# Power_management.net
KiCad netlist of a schematic drawn in Altium Designer
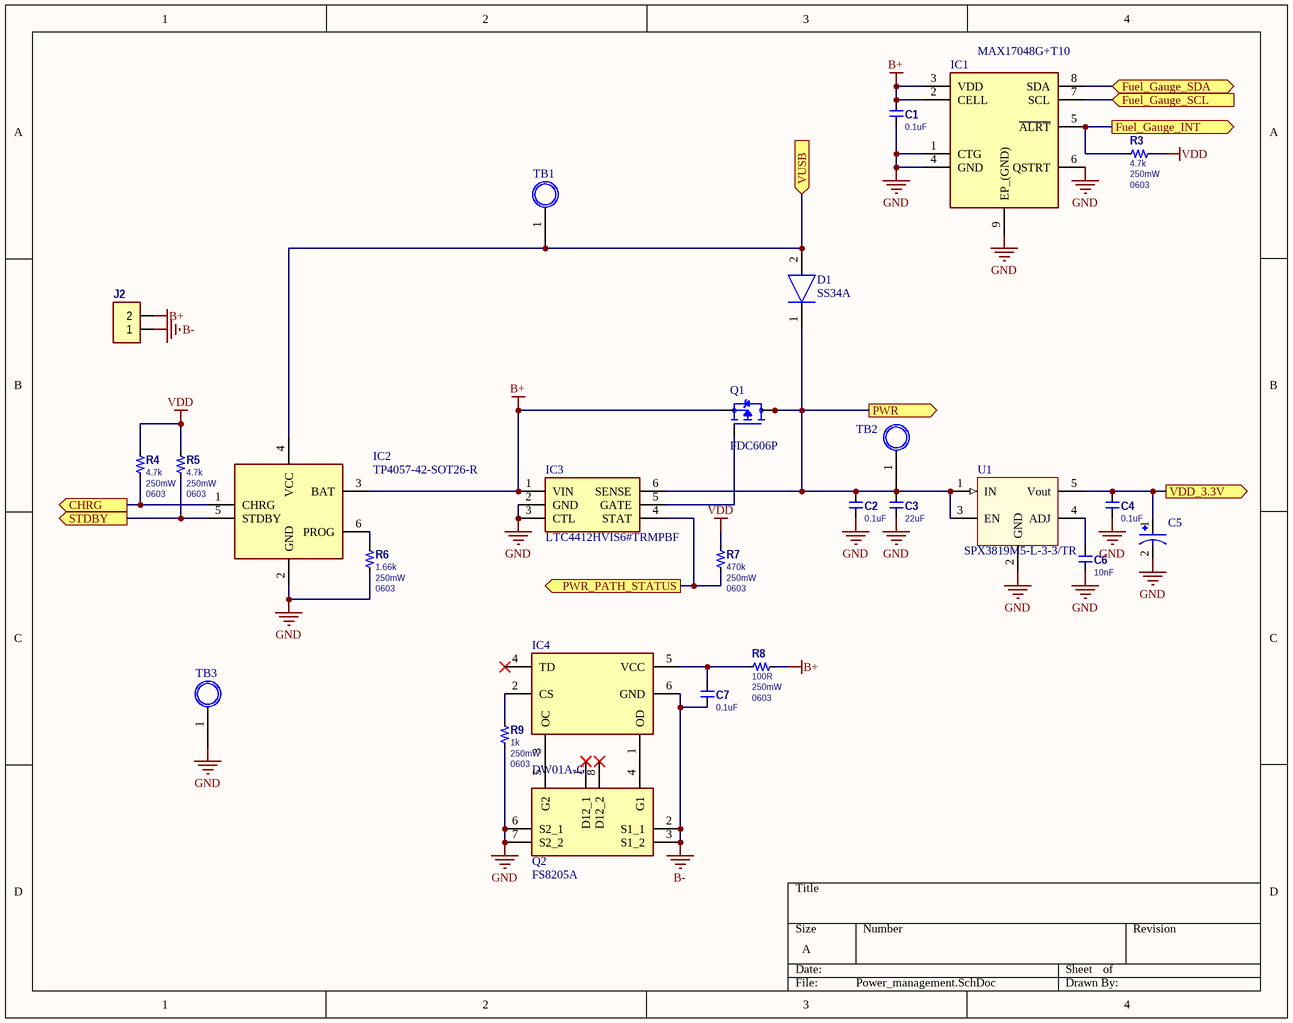
[diagram p0: Power_management.SchDoc]

(export (version "E")
  (design (tool "Eeschema 10.0.6"))
  (components
    (comp (ref "C1")
      (value "0.1uF")
      (footprint "0603-C")
      (description "CAP")
      (fields
        (field (name "MANUFACTURER") "TDK EPCOS")
        (field (name "MANUFACTURER PART NUMBER") "B37941K9105K62")
      )
      (libsource (lib "Safety_Lock") (part "CAP"))
    )
    (comp (ref "C2")
      (value "0.1uF")
      (footprint "0603-C")
      (description "CAP")
      (fields
        (field (name "MANUFACTURER") "TDK EPCOS")
        (field (name "MANUFACTURER PART NUMBER") "B37941K9105K62")
      )
      (libsource (lib "Safety_Lock") (part "CAP"))
    )
    (comp (ref "C3")
      (value "22uF")
      (footprint "0603-C")
      (description "CAP")
      (fields
        (field (name "MANUFACTURER") "TDK EPCOS")
        (field (name "MANUFACTURER PART NUMBER") "B37941K9105K62")
      )
      (libsource (lib "Safety_Lock") (part "CAP"))
    )
    (comp (ref "C4")
      (value "0.1uF")
      (footprint "0603-C")
      (description "CAP")
      (fields
        (field (name "MANUFACTURER") "TDK EPCOS")
        (field (name "MANUFACTURER PART NUMBER") "B37941K9105K62")
      )
      (libsource (lib "Safety_Lock") (part "CAP"))
    )
    (comp (ref "C5")
      (value "T493X227K010BH6420_220uF")
      (footprint "CAPPM7343X430N")
      (fields (field (name "MP") "T493X227K010BH6420") (field (name "MF") "Kemet"))
      (libsource (lib "Safety_Lock") (part "T493X227K010BH6420_220uF"))
    )
    (comp (ref "C6")
      (value "10nF")
      (footprint "0603-C")
      (description "CAP")
      (fields
        (field (name "MANUFACTURER") "TDK EPCOS")
        (field (name "MANUFACTURER PART NUMBER") "B37941K9105K62")
      )
      (libsource (lib "Safety_Lock") (part "CAP"))
    )
    (comp (ref "C7")
      (value "0.1uF")
      (footprint "0603-C")
      (description "CAP")
      (fields
        (field (name "MANUFACTURER") "TDK EPCOS")
        (field (name "MANUFACTURER PART NUMBER") "B37941K9105K62")
      )
      (libsource (lib "Safety_Lock") (part "CAP"))
    )
    (comp (ref "D1")
      (value "SS34A")
      (footprint "DIOM5026X262N")
      (description "Diode")
      (libsource (lib "Safety_Lock") (part "SS34A"))
    )
    (comp (ref "IC1")
      (value "MAX17048G+T10")
      (footprint "SON50P200X200X80-9N-D")
      (description "Integrated Circuit")
      (fields (field (name "MOUSER PART NUMBER") "700-MAX17048G+T10"))
      (libsource (lib "Safety_Lock") (part "MAX17048G+T10"))
    )
    (comp (ref "IC2")
      (value "TP4057-42-SOT26-R")
      (footprint "SOT95P280X125-6N")
      (description "Integrated Circuit")
      (libsource (lib "Safety_Lock") (part "TP4057-42-SOT26-R"))
    )
    (comp (ref "IC3")
      (value "LTC4412HVIS6#TRMPBF")
      (footprint "SOT95P280X100-6N")
      (description "Integrated Circuit")
      (fields (field (name "MOUSER PART NUMBER") "584-C4412HVIS6TRMPBF"))
      (libsource (lib "Safety_Lock") (part "LTC4412HVIS6#TRMPBF"))
    )
    (comp (ref "IC4")
      (value "DW01A-G")
      (footprint "SOT95P280X135-6N")
      (description "Integrated Circuit")
      (libsource (lib "Safety_Lock") (part "DW01A-G"))
    )
    (comp (ref "J2")
      (value "455-2247-ND")
      (footprint "CON_HDR1x2")
      (libsource (lib "Safety_Lock") (part "CON_HDR1x2"))
    )
    (comp (ref "Q1")
      (value "FDC606P")
      (footprint "SUPERSOT-6")
      (description "P-Channel 12V 6A (Ta) 1.6W (Ta) Surface Mount SuperSOTâ„¢-6")
      (fields (field (name "MF") "ON Semiconductor"))
      (libsource (lib "Safety_Lock") (part "FDC606P"))
    )
    (comp (ref "Q2")
      (value "FS8205A")
      (footprint "SOP65P640X120-8N")
      (description "Transistor")
      (libsource (lib "Safety_Lock") (part "FS8205A"))
    )
    (comp (ref "R3")
      (value "4.7k")
      (footprint "0603-R")
      (fields
        (field (name "MANUFACTURER") "Panasonic")
        (field (name "MANUFACTURER PART NUMBER") "ERJ-8GEYJ621V")
        (field (name "TOLERANCE") "5%")
        (field (name "POWER RATING") "250mW")
        (field (name "CASE/PACKAGE") "0603")
      )
      (libsource (lib "Safety_Lock") (part "Res"))
    )
    (comp (ref "R4")
      (value "4.7k")
      (footprint "0603-R")
      (fields
        (field (name "MANUFACTURER") "Panasonic")
        (field (name "MANUFACTURER PART NUMBER") "ERJ-8GEYJ621V")
        (field (name "TOLERANCE") "5%")
        (field (name "POWER RATING") "250mW")
        (field (name "CASE/PACKAGE") "0603")
      )
      (libsource (lib "Safety_Lock") (part "Res"))
    )
    (comp (ref "R5")
      (value "4.7k")
      (footprint "0603-R")
      (fields
        (field (name "MANUFACTURER") "Panasonic")
        (field (name "MANUFACTURER PART NUMBER") "ERJ-8GEYJ621V")
        (field (name "TOLERANCE") "5%")
        (field (name "POWER RATING") "250mW")
        (field (name "CASE/PACKAGE") "0603")
      )
      (libsource (lib "Safety_Lock") (part "Res"))
    )
    (comp (ref "R6")
      (value "1.66k")
      (footprint "0603-R")
      (fields
        (field (name "MANUFACTURER") "Panasonic")
        (field (name "MANUFACTURER PART NUMBER") "ERJ-8GEYJ621V")
        (field (name "TOLERANCE") "5%")
        (field (name "POWER RATING") "250mW")
        (field (name "CASE/PACKAGE") "0603")
      )
      (libsource (lib "Safety_Lock") (part "Res"))
    )
    (comp (ref "R7")
      (value "470k")
      (footprint "0603-R")
      (fields
        (field (name "MANUFACTURER") "Panasonic")
        (field (name "MANUFACTURER PART NUMBER") "ERJ-8GEYJ621V")
        (field (name "TOLERANCE") "5%")
        (field (name "POWER RATING") "250mW")
        (field (name "CASE/PACKAGE") "0603")
      )
      (libsource (lib "Safety_Lock") (part "Res"))
    )
    (comp (ref "R8")
      (value "100R")
      (footprint "0603-R")
      (fields
        (field (name "MANUFACTURER") "Panasonic")
        (field (name "MANUFACTURER PART NUMBER") "ERJ-8GEYJ621V")
        (field (name "TOLERANCE") "5%")
        (field (name "POWER RATING") "250mW")
        (field (name "CASE/PACKAGE") "0603")
      )
      (libsource (lib "Safety_Lock") (part "Res"))
    )
    (comp (ref "R9")
      (value "1k")
      (footprint "0603-R")
      (fields
        (field (name "MANUFACTURER") "Panasonic")
        (field (name "MANUFACTURER PART NUMBER") "ERJ-8GEYJ621V")
        (field (name "TOLERANCE") "5%")
        (field (name "POWER RATING") "250mW")
        (field (name "CASE/PACKAGE") "0603")
      )
      (libsource (lib "Safety_Lock") (part "Res"))
    )
    (comp (ref "TB1")
      (value "Test_Pad")
      (footprint "Test_Pad")
      (libsource (lib "Safety_Lock") (part "Test_Pad"))
    )
    (comp (ref "TB2")
      (value "Test_Pad")
      (footprint "Test_Pad")
      (libsource (lib "Safety_Lock") (part "Test_Pad"))
    )
    (comp (ref "TB3")
      (value "Test_Pad")
      (footprint "Test_Pad")
      (libsource (lib "Safety_Lock") (part "Test_Pad"))
    )
    (comp (ref "U1")
      (value "SPX3819M5-L-3-3/TR")
      (footprint "SOT23-5")
      (description "Linear Voltage Regulator IC 1 Output 500mA SOT-23-5")
      (fields (field (name "MP") "SPX3819") (field (name "MF") "MaxLinear, Inc."))
      (libsource (lib "Safety_Lock") (part "SPX3819"))
    )
  )
  (nets
    (net (code "1") (name "/CHRG") (class "Default")
      (node (ref "IC2") (pin "1") (pinfunction "CHRG_1") (pintype "passive"))
      (node (ref "R4") (pin "2") (pinfunction "2_2") (pintype "passive"))
    )
    (net (code "2") (name "/Fuel_Gauge_INT") (class "Default")
      (node (ref "IC1") (pin "5") (pinfunction "~{ALRT}_5") (pintype "passive"))
      (node (ref "R3") (pin "1") (pinfunction "1_1") (pintype "passive"))
    )
    (net (code "3") (name "/Fuel_Gauge_SCL") (class "Default")
      (node (ref "IC1") (pin "7") (pinfunction "SCL_7") (pintype "passive"))
    )
    (net (code "4") (name "/Fuel_Gauge_SDA") (class "Default")
      (node (ref "IC1") (pin "8") (pinfunction "SDA_8") (pintype "passive"))
    )
    (net (code "5") (name "/PWR") (class "Default")
      (node (ref "C2") (pin "1") (pinfunction "1_1") (pintype "passive"))
      (node (ref "C3") (pin "1") (pinfunction "1_1") (pintype "passive"))
      (node (ref "D1") (pin "1") (pinfunction "K_1") (pintype "passive"))
      (node (ref "IC3") (pin "6") (pinfunction "SENSE_6") (pintype "passive"))
      (node (ref "Q1") (pin "1") (pinfunction "D_1") (pintype "passive"))
      (node (ref "Q1") (pin "2") (pinfunction "D_2") (pintype "passive"))
      (node (ref "Q1") (pin "5") (pinfunction "D_5") (pintype "passive"))
      (node (ref "Q1") (pin "6") (pinfunction "D_6") (pintype "passive"))
      (node (ref "TB2") (pin "1") (pinfunction "1_1") (pintype "passive"))
      (node (ref "U1") (pin "1") (pinfunction "IN_1") (pintype "input"))
      (node (ref "U1") (pin "3") (pinfunction "EN_3") (pintype "passive"))
    )
    (net (code "6") (name "/PWR_PATH_STATUS") (class "Default")
      (node (ref "IC3") (pin "4") (pinfunction "STAT_4") (pintype "passive"))
      (node (ref "R7") (pin "1") (pinfunction "1_1") (pintype "passive"))
    )
    (net (code "7") (name "/STDBY") (class "Default")
      (node (ref "IC2") (pin "5") (pinfunction "STDBY_5") (pintype "passive"))
      (node (ref "R5") (pin "2") (pinfunction "2_2") (pintype "passive"))
    )
    (net (code "8") (name "/VDD_3.3V") (class "Default")
      (node (ref "C4") (pin "1") (pinfunction "1_1") (pintype "passive"))
      (node (ref "C5") (pin "1") (pinfunction "1_1") (pintype "passive"))
      (node (ref "U1") (pin "5") (pinfunction "Vout_5") (pintype "passive"))
    )
    (net (code "9") (name "/VUSB") (class "Default")
      (node (ref "D1") (pin "2") (pinfunction "A_2") (pintype "passive"))
      (node (ref "IC2") (pin "4") (pinfunction "VCC_4") (pintype "passive"))
      (node (ref "TB1") (pin "1") (pinfunction "1_1") (pintype "passive"))
    )
    (net (code "10") (name "B+") (class "Default")
      (node (ref "C1") (pin "1") (pinfunction "1_1") (pintype "passive"))
      (node (ref "IC1") (pin "2") (pinfunction "CELL_2") (pintype "passive"))
      (node (ref "IC1") (pin "3") (pinfunction "VDD_3") (pintype "passive"))
      (node (ref "IC2") (pin "3") (pinfunction "BAT_3") (pintype "passive"))
      (node (ref "IC3") (pin "1") (pinfunction "VIN_1") (pintype "passive"))
      (node (ref "J2") (pin "2") (pinfunction "2_2") (pintype "passive"))
      (node (ref "Q1") (pin "4") (pinfunction "S_4") (pintype "passive"))
      (node (ref "R8") (pin "2") (pinfunction "2_2") (pintype "passive"))
    )
    (net (code "11") (name "B-") (class "Default")
      (node (ref "C7") (pin "2") (pinfunction "2_2") (pintype "passive"))
      (node (ref "IC4") (pin "6") (pinfunction "GND_6") (pintype "passive"))
      (node (ref "J2") (pin "1") (pinfunction "1_1") (pintype "passive"))
      (node (ref "Q2") (pin "2") (pinfunction "S1_1_2") (pintype "passive"))
      (node (ref "Q2") (pin "3") (pinfunction "S1_2_3") (pintype "passive"))
    )
    (net (code "12") (name "GND") (class "Default")
      (node (ref "C1") (pin "2") (pinfunction "2_2") (pintype "passive"))
      (node (ref "C2") (pin "2") (pinfunction "2_2") (pintype "passive"))
      (node (ref "C3") (pin "2") (pinfunction "2_2") (pintype "passive"))
      (node (ref "C4") (pin "2") (pinfunction "2_2") (pintype "passive"))
      (node (ref "C5") (pin "2") (pinfunction "2_2") (pintype "passive"))
      (node (ref "C6") (pin "2") (pinfunction "2_2") (pintype "passive"))
      (node (ref "IC1") (pin "1") (pinfunction "CTG_1") (pintype "passive"))
      (node (ref "IC1") (pin "4") (pinfunction "GND_4") (pintype "passive"))
      (node (ref "IC1") (pin "6") (pinfunction "QSTRT_6") (pintype "passive"))
      (node (ref "IC1") (pin "9") (pinfunction "EP_(GND)_9") (pintype "passive"))
      (node (ref "IC2") (pin "2") (pinfunction "GND_2") (pintype "passive"))
      (node (ref "IC3") (pin "2") (pinfunction "GND_2") (pintype "passive"))
      (node (ref "IC3") (pin "3") (pinfunction "CTL_3") (pintype "passive"))
      (node (ref "Q2") (pin "6") (pinfunction "S2_1_6") (pintype "passive"))
      (node (ref "Q2") (pin "7") (pinfunction "S2_2_7") (pintype "passive"))
      (node (ref "R6") (pin "2") (pinfunction "2_2") (pintype "passive"))
      (node (ref "R9") (pin "2") (pinfunction "2_2") (pintype "passive"))
      (node (ref "TB3") (pin "1") (pinfunction "1_1") (pintype "passive"))
      (node (ref "U1") (pin "2") (pinfunction "GND_2") (pintype "power_in"))
    )
    (net (code "13") (name "Net-(IC2-PROG)") (class "Default")
      (node (ref "IC2") (pin "6") (pinfunction "PROG_6") (pintype "passive"))
      (node (ref "R6") (pin "1") (pinfunction "1_1") (pintype "passive"))
    )
    (net (code "14") (name "Net-(IC3-GATE)") (class "Default")
      (node (ref "IC3") (pin "5") (pinfunction "GATE_5") (pintype "passive"))
      (node (ref "Q1") (pin "3") (pinfunction "G_3") (pintype "passive"))
    )
    (net (code "15") (name "Net-(IC4-CS)") (class "Default")
      (node (ref "IC4") (pin "2") (pinfunction "CS_2") (pintype "passive"))
      (node (ref "R9") (pin "1") (pinfunction "1_1") (pintype "passive"))
    )
    (net (code "16") (name "Net-(IC4-OC)") (class "Default")
      (node (ref "IC4") (pin "3") (pinfunction "OC_3") (pintype "passive"))
      (node (ref "Q2") (pin "5") (pinfunction "G2_5") (pintype "passive"))
    )
    (net (code "17") (name "Net-(IC4-OD)") (class "Default")
      (node (ref "IC4") (pin "1") (pinfunction "OD_1") (pintype "passive"))
      (node (ref "Q2") (pin "4") (pinfunction "G1_4") (pintype "passive"))
    )
    (net (code "18") (name "Net-(IC4-VCC)") (class "Default")
      (node (ref "C7") (pin "1") (pinfunction "1_1") (pintype "passive"))
      (node (ref "IC4") (pin "5") (pinfunction "VCC_5") (pintype "passive"))
      (node (ref "R8") (pin "1") (pinfunction "1_1") (pintype "passive"))
    )
    (net (code "19") (name "Net-(U1-ADJ)") (class "Default")
      (node (ref "C6") (pin "1") (pinfunction "1_1") (pintype "passive"))
      (node (ref "U1") (pin "4") (pinfunction "ADJ_4") (pintype "passive"))
    )
    (net (code "20") (name "VDD") (class "Default")
      (node (ref "R3") (pin "2") (pinfunction "2_2") (pintype "passive"))
      (node (ref "R4") (pin "1") (pinfunction "1_1") (pintype "passive"))
      (node (ref "R5") (pin "1") (pinfunction "1_1") (pintype "passive"))
      (node (ref "R7") (pin "2") (pinfunction "2_2") (pintype "passive"))
    )
    (net (code "21") (name "unconnected-(IC4-TD-Pad4)") (class "Default")
      (node (ref "IC4") (pin "4") (pinfunction "TD_4") (pintype "passive+no_connect"))
    )
    (net (code "22") (name "unconnected-(Q2-D12_1-Pad1)") (class "Default")
      (node (ref "Q2") (pin "1") (pinfunction "D12_1_1") (pintype "passive+no_connect"))
    )
    (net (code "23") (name "unconnected-(Q2-D12_2-Pad8)") (class "Default")
      (node (ref "Q2") (pin "8") (pinfunction "D12_2_8") (pintype "passive+no_connect"))
    )
  )
)
